# rs-485-power-injector-leanpcb.net
KiCad netlist of a schematic drawn in EAGLE
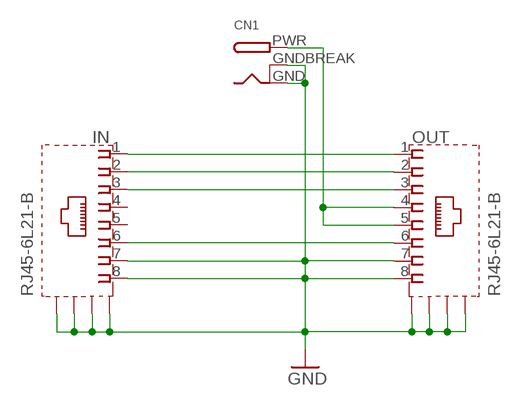
[diagram p0: schematic, sheet 1]

(export (version "E")
  (design (tool "Eeschema 10.0.6"))
  (components
    (comp (ref "CN1")
      (value "DCBARRELPTH")
      (footprint "eagle-import:DCJACK_2MM_PTH")
      (libsource (lib "eagle-import") (part "DCBARRELPTH"))
    )
    (comp (ref "IN")
      (value "RJ45-6L21-B")
      (footprint "eagle-import:RJ45-SHIELD1")
      (libsource (lib "eagle-import") (part "RJ4521-B-6L"))
    )
    (comp (ref "OUT")
      (value "RJ45-6L21-B")
      (footprint "eagle-import:RJ45-SHIELD1")
      (libsource (lib "eagle-import") (part "RJ4521-B-6L"))
    )
  )
  (nets
    (net (code "1") (name "GND") (class "Default")
      (node (ref "CN1") (pin "GND") (pinfunction "GND_GND") (pintype "power_in"))
      (node (ref "CN1") (pin "GNDBREAK") (pinfunction "GNDBREAK_GNDBREAK") (pintype "power_in"))
      (node (ref "IN") (pin "7") (pinfunction "7_7") (pintype "passive"))
      (node (ref "IN") (pin "8") (pinfunction "8_8") (pintype "passive"))
      (node (ref "IN") (pin "S1") (pinfunction "S_S1") (pintype "passive"))
      (node (ref "IN") (pin "S2") (pinfunction "S_S2") (pintype "passive"))
      (node (ref "IN") (pin "S3") (pinfunction "S_S3") (pintype "passive"))
      (node (ref "IN") (pin "S4") (pinfunction "S_S4") (pintype "passive"))
      (node (ref "OUT") (pin "7") (pinfunction "7_7") (pintype "passive"))
      (node (ref "OUT") (pin "8") (pinfunction "8_8") (pintype "passive"))
      (node (ref "OUT") (pin "S1") (pinfunction "S_S1") (pintype "passive"))
      (node (ref "OUT") (pin "S2") (pinfunction "S_S2") (pintype "passive"))
      (node (ref "OUT") (pin "S3") (pinfunction "S_S3") (pintype "passive"))
      (node (ref "OUT") (pin "S4") (pinfunction "S_S4") (pintype "passive"))
    )
    (net (code "2") (name "Net-(CN1-PadPWR)") (class "Default")
      (node (ref "CN1") (pin "PWR") (pinfunction "PWR_PWR") (pintype "power_in"))
      (node (ref "OUT") (pin "4") (pinfunction "4_4") (pintype "passive"))
      (node (ref "OUT") (pin "5") (pinfunction "5_5") (pintype "passive"))
    )
    (net (code "3") (name "Net-(IN-Pad1)") (class "Default")
      (node (ref "IN") (pin "1") (pinfunction "1_1") (pintype "passive"))
      (node (ref "OUT") (pin "1") (pinfunction "1_1") (pintype "passive"))
    )
    (net (code "4") (name "Net-(IN-Pad2)") (class "Default")
      (node (ref "IN") (pin "2") (pinfunction "2_2") (pintype "passive"))
      (node (ref "OUT") (pin "2") (pinfunction "2_2") (pintype "passive"))
    )
    (net (code "5") (name "Net-(IN-Pad3)") (class "Default")
      (node (ref "IN") (pin "3") (pinfunction "3_3") (pintype "passive"))
      (node (ref "OUT") (pin "3") (pinfunction "3_3") (pintype "passive"))
    )
    (net (code "6") (name "Net-(IN-Pad6)") (class "Default")
      (node (ref "IN") (pin "6") (pinfunction "6_6") (pintype "passive"))
      (node (ref "OUT") (pin "6") (pinfunction "6_6") (pintype "passive"))
    )
    (net (code "7") (name "unconnected-(IN-Pad4)") (class "Default")
      (node (ref "IN") (pin "4") (pinfunction "4_4") (pintype "passive"))
    )
    (net (code "8") (name "unconnected-(IN-Pad5)") (class "Default")
      (node (ref "IN") (pin "5") (pinfunction "5_5") (pintype "passive"))
    )
  )
)
